# SCH_Flight-Computer-V3_2024-07-16.net
KiCad netlist of a schematic drawn in EasyEDA
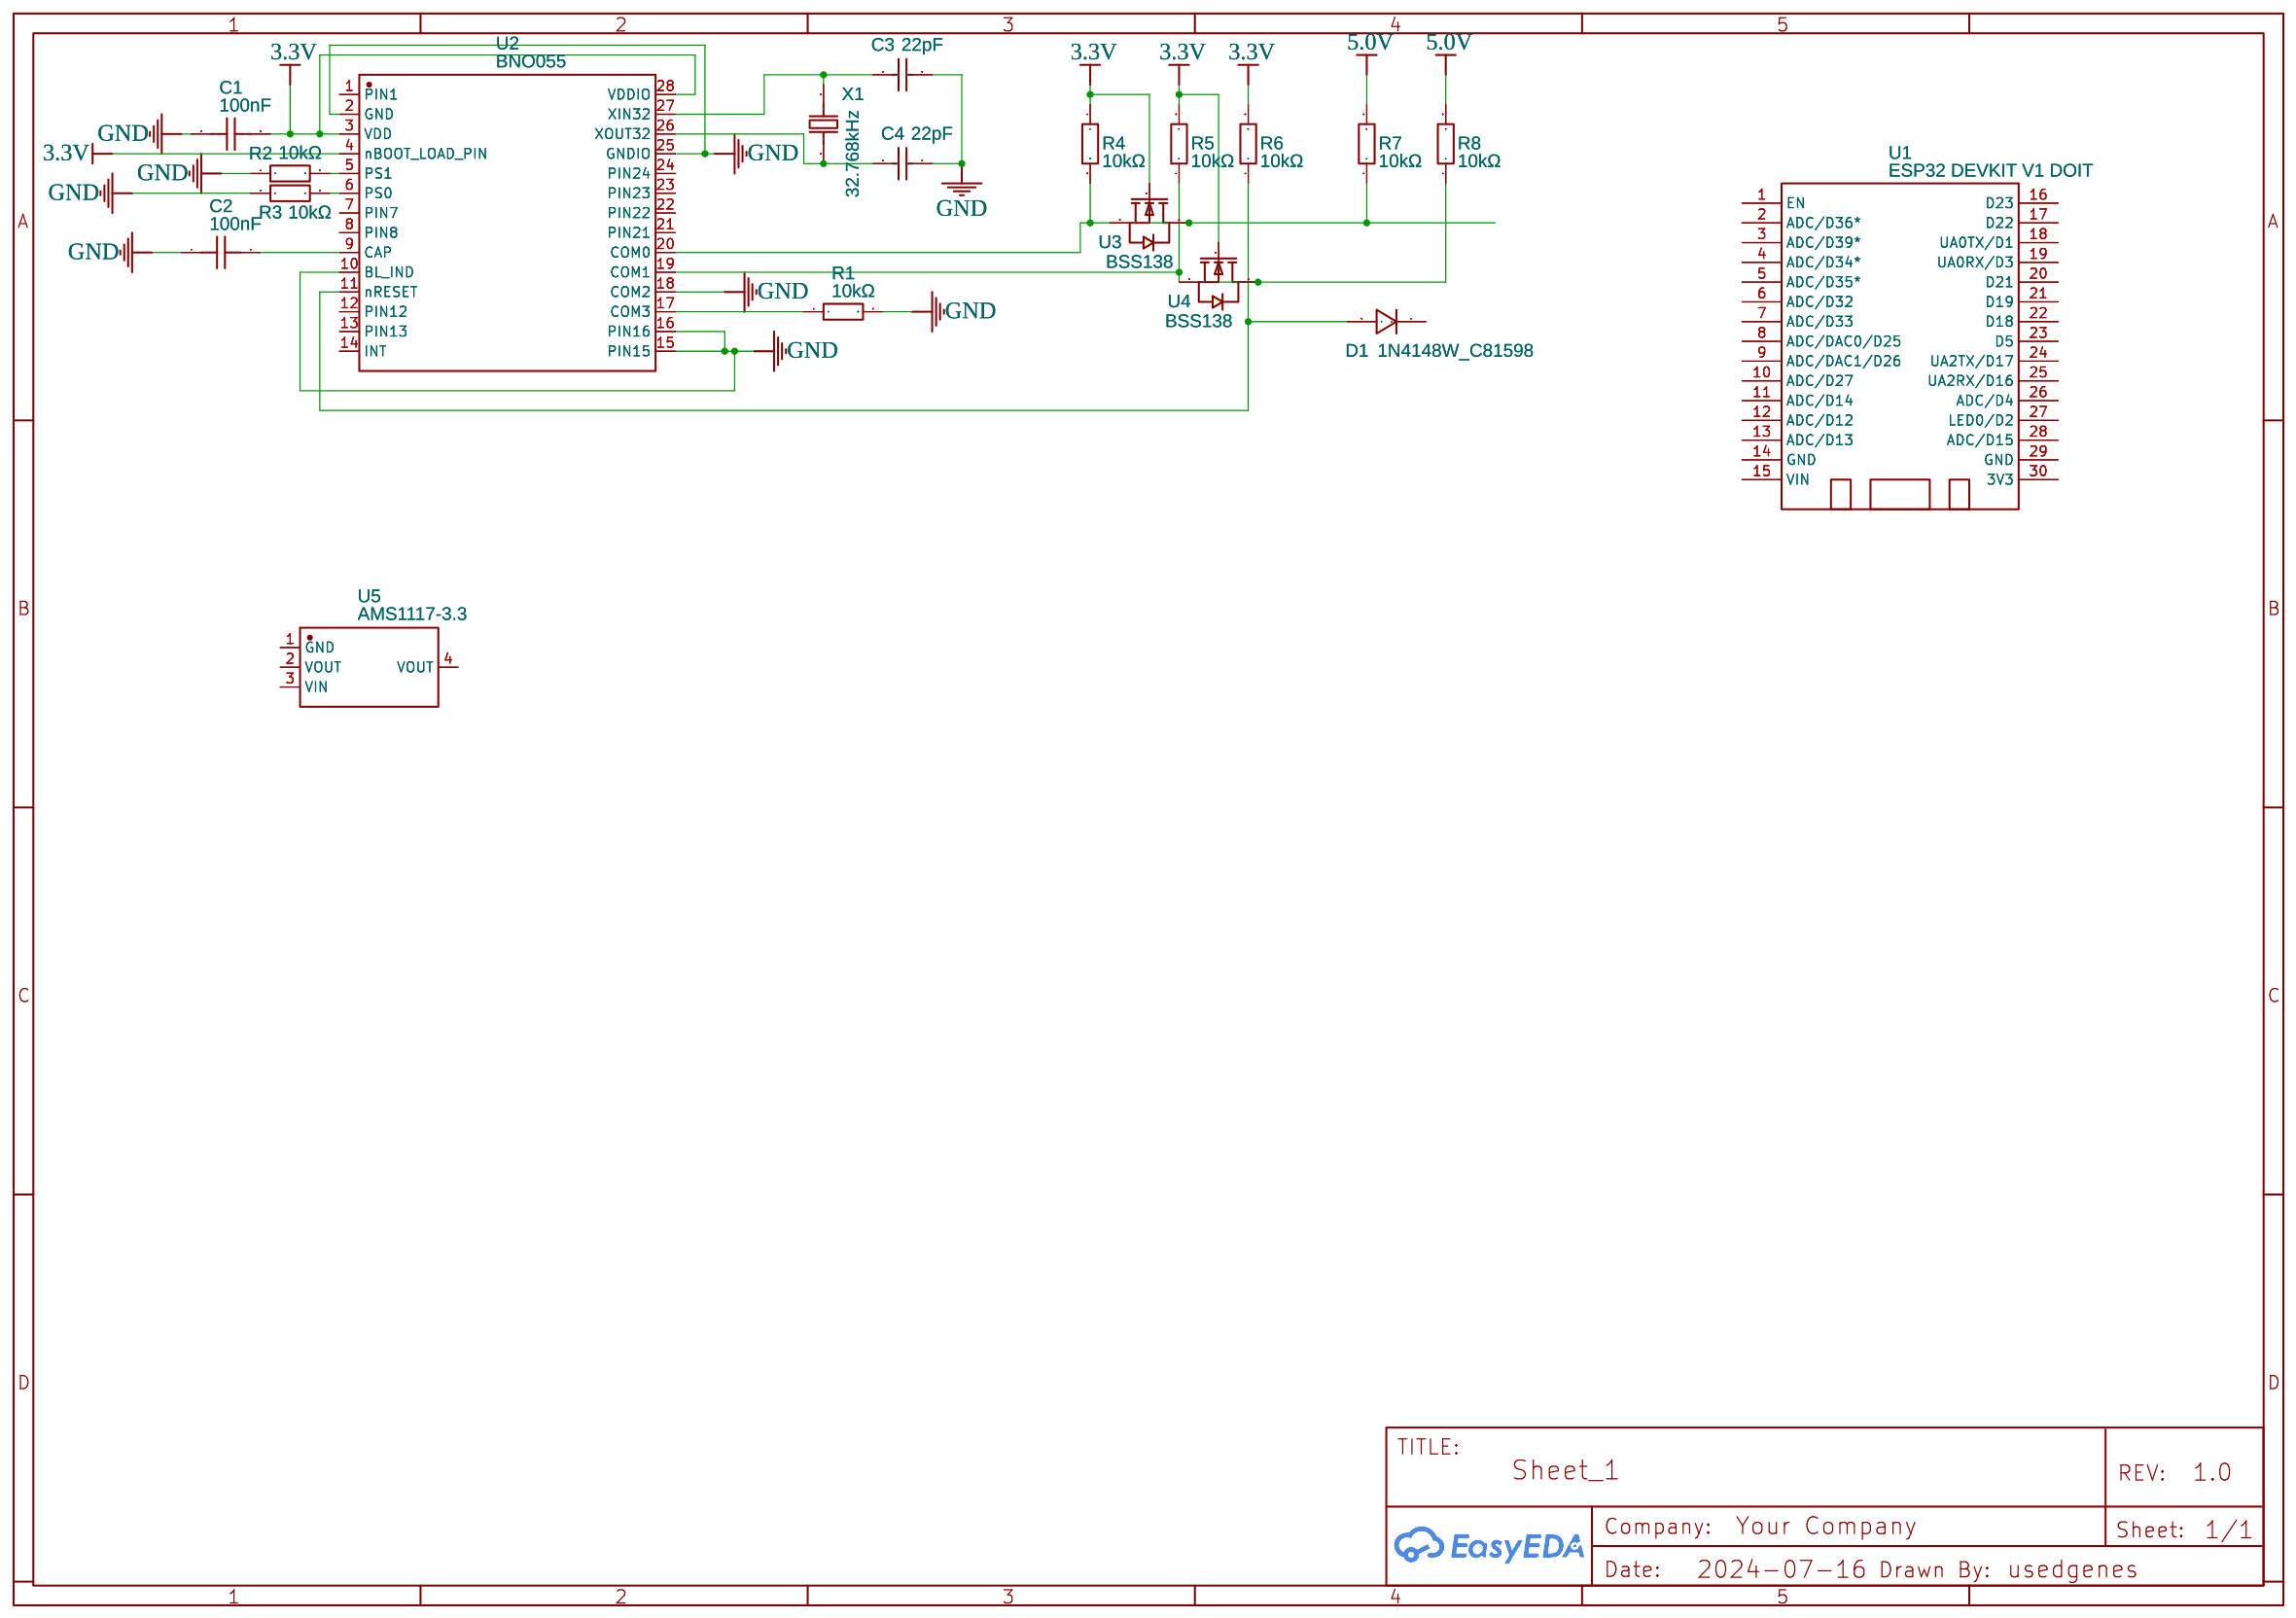
[diagram p0: schematic sheet]

(export (version "E")
  (design (tool "Eeschema 10.0.6"))
  (components
    (comp (ref "C1")
      (value "100nF")
      (fields
        (field (name "Manufacturer Part") "CC0603KRX7R9BB104")
        (field (name "Manufacturer") "YAGEO(国巨)")
      )
      (libsource (lib "") (part "CC0603KRX7R9BB104"))
    )
    (comp (ref "C2")
      (value "100nF")
      (fields
        (field (name "Manufacturer Part") "CC0603KRX7R9BB104")
        (field (name "Manufacturer") "YAGEO(国巨)")
      )
      (libsource (lib "") (part "CC0603KRX7R9BB104"))
    )
    (comp (ref "C3")
      (value "22pF")
      (fields (field (name "Manufacturer Part") "0402CG220J500NT") (field (name "Manufacturer") "FH(风华)"))
      (libsource (lib "") (part "0402CG220J500NT"))
    )
    (comp (ref "C4")
      (value "22pF")
      (fields (field (name "Manufacturer Part") "0402CG220J500NT") (field (name "Manufacturer") "FH(风华)"))
      (libsource (lib "") (part "0402CG220J500NT"))
    )
    (comp (ref "D1")
      (value "1N4148W_C81598")
      (fields (field (name "Manufacturer Part") "1N4148W") (field (name "Manufacturer") "ST(先科)"))
      (libsource (lib "") (part "1N4148W_C81598"))
    )
    (comp (ref "R1")
      (value "10kΩ")
      (fields
        (field (name "Manufacturer Part") "0402WGF1002TCE")
        (field (name "Manufacturer") "UNI-ROYAL(厚声)")
      )
      (libsource (lib "") (part "0402WGF1002TCE"))
    )
    (comp (ref "R2")
      (value "10kΩ")
      (fields
        (field (name "Manufacturer Part") "0402WGF1002TCE")
        (field (name "Manufacturer") "UNI-ROYAL(厚声)")
      )
      (libsource (lib "") (part "0402WGF1002TCE"))
    )
    (comp (ref "R3")
      (value "10kΩ")
      (fields
        (field (name "Manufacturer Part") "0402WGF1002TCE")
        (field (name "Manufacturer") "UNI-ROYAL(厚声)")
      )
      (libsource (lib "") (part "0402WGF1002TCE"))
    )
    (comp (ref "R4")
      (value "10kΩ")
      (fields
        (field (name "Manufacturer Part") "0402WGF1002TCE")
        (field (name "Manufacturer") "UNI-ROYAL(厚声)")
      )
      (libsource (lib "") (part "0402WGF1002TCE_2"))
    )
    (comp (ref "R5")
      (value "10kΩ")
      (fields
        (field (name "Manufacturer Part") "0402WGF1002TCE")
        (field (name "Manufacturer") "UNI-ROYAL(厚声)")
      )
      (libsource (lib "") (part "0402WGF1002TCE_1"))
    )
    (comp (ref "R6")
      (value "10kΩ")
      (fields
        (field (name "Manufacturer Part") "0402WGF1002TCE")
        (field (name "Manufacturer") "UNI-ROYAL(厚声)")
      )
      (libsource (lib "") (part "0402WGF1002TCE_1"))
    )
    (comp (ref "R7")
      (value "10kΩ")
      (fields
        (field (name "Manufacturer Part") "0402WGF1002TCE")
        (field (name "Manufacturer") "UNI-ROYAL(厚声)")
      )
      (libsource (lib "") (part "0402WGF1002TCE_1"))
    )
    (comp (ref "R8")
      (value "10kΩ")
      (fields
        (field (name "Manufacturer Part") "0402WGF1002TCE")
        (field (name "Manufacturer") "UNI-ROYAL(厚声)")
      )
      (libsource (lib "") (part "0402WGF1002TCE_1"))
    )
    (comp (ref "U1") (value "ESP32 DEVKIT V1 DOIT") (libsource (lib "") (part "ESP32 DEVKIT V1 DOIT")))
    (comp (ref "U2")
      (value "BNO055")
      (fields (field (name "Manufacturer") "Bosch(博世)"))
      (libsource (lib "") (part "BNO055"))
    )
    (comp (ref "U3")
      (value "BSS138")
      (fields (field (name "Manufacturer") "宏迦橙"))
      (libsource (lib "") (part "BSS138_C7420339"))
    )
    (comp (ref "U4")
      (value "BSS138")
      (fields (field (name "Manufacturer") "宏迦橙"))
      (libsource (lib "") (part "BSS138_C7420339"))
    )
    (comp (ref "U5")
      (value "AMS1117-3.3")
      (fields (field (name "Manufacturer") "AMS"))
      (libsource (lib "") (part "AMS1117-3.3"))
    )
    (comp (ref "X1")
      (value "32.768kHz")
      (fields
        (field (name "Manufacturer Part") "SC-32S32.768kHz20PPM12.5pF")
        (field (name "Manufacturer") "Seiko(精工)")
      )
      (libsource (lib "") (part "SC-32S32.768kHz20PPM12.5pF"))
    )
  )
  (nets
    (net (code "1") (name "3.3V") (class "Default")
      (node (ref "C1") (pin "2") (pinfunction "2_2") (pintype "unspecified"))
      (node (ref "R4") (pin "1") (pinfunction "1_1") (pintype "input"))
      (node (ref "R5") (pin "2") (pinfunction "2_2") (pintype "input"))
      (node (ref "R6") (pin "2") (pinfunction "2_2") (pintype "input"))
      (node (ref "U2") (pin "28") (pinfunction "VDDIO_28") (pintype "unspecified"))
      (node (ref "U2") (pin "3") (pinfunction "VDD_3") (pintype "unspecified"))
      (node (ref "U2") (pin "4") (pinfunction "nBOOT_LOAD_PIN_4") (pintype "unspecified"))
      (node (ref "U3") (pin "1") (pinfunction "G_1") (pintype "unspecified"))
      (node (ref "U4") (pin "1") (pinfunction "G_1") (pintype "unspecified"))
    )
    (net (code "2") (name "5.0V") (class "Default")
      (node (ref "R7") (pin "2") (pinfunction "2_2") (pintype "input"))
      (node (ref "R8") (pin "2") (pinfunction "2_2") (pintype "input"))
    )
    (net (code "3") (name "GND") (class "Default")
      (node (ref "C1") (pin "1") (pinfunction "1_1") (pintype "unspecified"))
      (node (ref "C2") (pin "1") (pinfunction "1_1") (pintype "unspecified"))
      (node (ref "C3") (pin "2") (pinfunction "2_2") (pintype "input"))
      (node (ref "C4") (pin "2") (pinfunction "2_2") (pintype "input"))
      (node (ref "R1") (pin "2") (pinfunction "2_2") (pintype "input"))
      (node (ref "R2") (pin "1") (pinfunction "1_1") (pintype "input"))
      (node (ref "R3") (pin "1") (pinfunction "1_1") (pintype "input"))
      (node (ref "U2") (pin "10") (pinfunction "BL_IND_10") (pintype "unspecified"))
      (node (ref "U2") (pin "15") (pinfunction "PIN15_15") (pintype "unspecified"))
      (node (ref "U2") (pin "16") (pinfunction "PIN16_16") (pintype "unspecified"))
      (node (ref "U2") (pin "18") (pinfunction "COM2_18") (pintype "unspecified"))
      (node (ref "U2") (pin "2") (pinfunction "GND_2") (pintype "unspecified"))
      (node (ref "U2") (pin "25") (pinfunction "GNDIO_25") (pintype "unspecified"))
    )
    (net (code "4") (name "Net-(D1-A)") (class "Default")
      (node (ref "D1") (pin "2") (pinfunction "A_2") (pintype "unspecified"))
      (node (ref "R6") (pin "1") (pinfunction "1_1") (pintype "input"))
      (node (ref "U2") (pin "11") (pinfunction "nRESET_11") (pintype "unspecified"))
    )
    (net (code "5") (name "Net-(U2-CAP)") (class "Default")
      (node (ref "C2") (pin "2") (pinfunction "2_2") (pintype "unspecified"))
      (node (ref "U2") (pin "9") (pinfunction "CAP_9") (pintype "unspecified"))
    )
    (net (code "6") (name "Net-(U2-COM0)") (class "Default")
      (node (ref "R4") (pin "2") (pinfunction "2_2") (pintype "input"))
      (node (ref "U2") (pin "20") (pinfunction "COM0_20") (pintype "unspecified"))
      (node (ref "U3") (pin "2") (pinfunction "S_2") (pintype "unspecified"))
    )
    (net (code "7") (name "Net-(U2-COM1)") (class "Default")
      (node (ref "R5") (pin "1") (pinfunction "1_1") (pintype "input"))
      (node (ref "U2") (pin "19") (pinfunction "COM1_19") (pintype "unspecified"))
      (node (ref "U4") (pin "2") (pinfunction "S_2") (pintype "unspecified"))
    )
    (net (code "8") (name "Net-(U2-COM3)") (class "Default")
      (node (ref "R1") (pin "1") (pinfunction "1_1") (pintype "input"))
      (node (ref "U2") (pin "17") (pinfunction "COM3_17") (pintype "unspecified"))
    )
    (net (code "9") (name "Net-(U2-PS0)") (class "Default")
      (node (ref "R3") (pin "2") (pinfunction "2_2") (pintype "input"))
      (node (ref "U2") (pin "6") (pinfunction "PS0_6") (pintype "unspecified"))
    )
    (net (code "10") (name "Net-(U2-PS1)") (class "Default")
      (node (ref "R2") (pin "2") (pinfunction "2_2") (pintype "input"))
      (node (ref "U2") (pin "5") (pinfunction "PS1_5") (pintype "unspecified"))
    )
    (net (code "11") (name "Net-(U2-XIN32)") (class "Default")
      (node (ref "C3") (pin "1") (pinfunction "1_1") (pintype "input"))
      (node (ref "U2") (pin "27") (pinfunction "XIN32_27") (pintype "unspecified"))
      (node (ref "X1") (pin "2") (pinfunction "2_2") (pintype "unspecified"))
    )
    (net (code "12") (name "Net-(U2-XOUT32)") (class "Default")
      (node (ref "C4") (pin "1") (pinfunction "1_1") (pintype "input"))
      (node (ref "U2") (pin "26") (pinfunction "XOUT32_26") (pintype "unspecified"))
      (node (ref "X1") (pin "1") (pinfunction "1_1") (pintype "unspecified"))
    )
    (net (code "13") (name "Net-(U3-D)") (class "Default")
      (node (ref "R7") (pin "1") (pinfunction "1_1") (pintype "input"))
      (node (ref "U3") (pin "3") (pinfunction "D_3") (pintype "unspecified"))
    )
    (net (code "14") (name "Net-(U4-D)") (class "Default")
      (node (ref "R8") (pin "1") (pinfunction "1_1") (pintype "input"))
      (node (ref "U4") (pin "3") (pinfunction "D_3") (pintype "unspecified"))
    )
    (net (code "15") (name "unconnected-(D1-K-Pad1)") (class "Default")
      (node (ref "D1") (pin "1") (pinfunction "K_1") (pintype "unspecified"))
    )
    (net (code "16") (name "unconnected-(U1-3V3-Pad30)") (class "Default")
      (node (ref "U1") (pin "30") (pinfunction "3V3_30") (pintype "bidirectional"))
    )
    (net (code "17") (name "unconnected-(U1-ADC{slash}D4-Pad26)") (class "Default")
      (node (ref "U1") (pin "26") (pinfunction "ADC/D4_26") (pintype "bidirectional"))
    )
    (net (code "18") (name "unconnected-(U1-ADC{slash}D12-Pad12)") (class "Default")
      (node (ref "U1") (pin "12") (pinfunction "ADC/D12_12") (pintype "bidirectional"))
    )
    (net (code "19") (name "unconnected-(U1-ADC{slash}D13-Pad13)") (class "Default")
      (node (ref "U1") (pin "13") (pinfunction "ADC/D13_13") (pintype "bidirectional"))
    )
    (net (code "20") (name "unconnected-(U1-ADC{slash}D14-Pad11)") (class "Default")
      (node (ref "U1") (pin "11") (pinfunction "ADC/D14_11") (pintype "bidirectional"))
    )
    (net (code "21") (name "unconnected-(U1-ADC{slash}D15-Pad28)") (class "Default")
      (node (ref "U1") (pin "28") (pinfunction "ADC/D15_28") (pintype "bidirectional"))
    )
    (net (code "22") (name "unconnected-(U1-ADC{slash}D27-Pad10)") (class "Default")
      (node (ref "U1") (pin "10") (pinfunction "ADC/D27_10") (pintype "bidirectional"))
    )
    (net (code "23") (name "unconnected-(U1-ADC{slash}D32-Pad6)") (class "Default")
      (node (ref "U1") (pin "6") (pinfunction "ADC/D32_6") (pintype "bidirectional"))
    )
    (net (code "24") (name "unconnected-(U1-ADC{slash}D33-Pad7)") (class "Default")
      (node (ref "U1") (pin "7") (pinfunction "ADC/D33_7") (pintype "bidirectional"))
    )
    (net (code "25") (name "unconnected-(U1-ADC{slash}D34*-Pad4)") (class "Default")
      (node (ref "U1") (pin "4") (pinfunction "ADC/D34*_4") (pintype "input"))
    )
    (net (code "26") (name "unconnected-(U1-ADC{slash}D35*-Pad5)") (class "Default")
      (node (ref "U1") (pin "5") (pinfunction "ADC/D35*_5") (pintype "input"))
    )
    (net (code "27") (name "unconnected-(U1-ADC{slash}D36*-Pad2)") (class "Default")
      (node (ref "U1") (pin "2") (pinfunction "ADC/D36*_2") (pintype "input"))
    )
    (net (code "28") (name "unconnected-(U1-ADC{slash}D39*-Pad3)") (class "Default")
      (node (ref "U1") (pin "3") (pinfunction "ADC/D39*_3") (pintype "input"))
    )
    (net (code "29") (name "unconnected-(U1-ADC{slash}DAC0{slash}D25-Pad8)") (class "Default")
      (node (ref "U1") (pin "8") (pinfunction "ADC/DAC0/D25_8") (pintype "bidirectional"))
    )
    (net (code "30") (name "unconnected-(U1-ADC{slash}DAC1{slash}D26-Pad9)") (class "Default")
      (node (ref "U1") (pin "9") (pinfunction "ADC/DAC1/D26_9") (pintype "bidirectional"))
    )
    (net (code "31") (name "unconnected-(U1-D5-Pad23)") (class "Default")
      (node (ref "U1") (pin "23") (pinfunction "D5_23") (pintype "bidirectional"))
    )
    (net (code "32") (name "unconnected-(U1-D18-Pad22)") (class "Default")
      (node (ref "U1") (pin "22") (pinfunction "D18_22") (pintype "bidirectional"))
    )
    (net (code "33") (name "unconnected-(U1-D19-Pad21)") (class "Default")
      (node (ref "U1") (pin "21") (pinfunction "D19_21") (pintype "bidirectional"))
    )
    (net (code "34") (name "unconnected-(U1-D21-Pad20)") (class "Default")
      (node (ref "U1") (pin "20") (pinfunction "D21_20") (pintype "bidirectional"))
    )
    (net (code "35") (name "unconnected-(U1-D22-Pad17)") (class "Default")
      (node (ref "U1") (pin "17") (pinfunction "D22_17") (pintype "bidirectional"))
    )
    (net (code "36") (name "unconnected-(U1-D23-Pad16)") (class "Default")
      (node (ref "U1") (pin "16") (pinfunction "D23_16") (pintype "bidirectional"))
    )
    (net (code "37") (name "unconnected-(U1-EN-Pad1)") (class "Default")
      (node (ref "U1") (pin "1") (pinfunction "EN_1") (pintype "bidirectional"))
    )
    (net (code "38") (name "unconnected-(U1-GND-Pad14)") (class "Default")
      (node (ref "U1") (pin "14") (pinfunction "GND_14") (pintype "bidirectional"))
    )
    (net (code "39") (name "unconnected-(U1-GND-Pad29)") (class "Default")
      (node (ref "U1") (pin "29") (pinfunction "GND_29") (pintype "bidirectional"))
    )
    (net (code "40") (name "unconnected-(U1-LED0{slash}D2-Pad27)") (class "Default")
      (node (ref "U1") (pin "27") (pinfunction "LED0/D2_27") (pintype "bidirectional"))
    )
    (net (code "41") (name "unconnected-(U1-UA0RX{slash}D3-Pad19)") (class "Default")
      (node (ref "U1") (pin "19") (pinfunction "UA0RX/D3_19") (pintype "bidirectional"))
    )
    (net (code "42") (name "unconnected-(U1-UA0TX{slash}D1-Pad18)") (class "Default")
      (node (ref "U1") (pin "18") (pinfunction "UA0TX/D1_18") (pintype "bidirectional"))
    )
    (net (code "43") (name "unconnected-(U1-UA2RX{slash}D16-Pad25)") (class "Default")
      (node (ref "U1") (pin "25") (pinfunction "UA2RX/D16_25") (pintype "bidirectional"))
    )
    (net (code "44") (name "unconnected-(U1-UA2TX{slash}D17-Pad24)") (class "Default")
      (node (ref "U1") (pin "24") (pinfunction "UA2TX/D17_24") (pintype "bidirectional"))
    )
    (net (code "45") (name "unconnected-(U1-VIN-Pad15)") (class "Default")
      (node (ref "U1") (pin "15") (pinfunction "VIN_15") (pintype "input"))
    )
    (net (code "46") (name "unconnected-(U2-INT-Pad14)") (class "Default")
      (node (ref "U2") (pin "14") (pinfunction "INT_14") (pintype "unspecified"))
    )
    (net (code "47") (name "unconnected-(U2-PIN1-Pad1)") (class "Default")
      (node (ref "U2") (pin "1") (pinfunction "PIN1_1") (pintype "unspecified"))
    )
    (net (code "48") (name "unconnected-(U2-PIN7-Pad7)") (class "Default")
      (node (ref "U2") (pin "7") (pinfunction "PIN7_7") (pintype "unspecified"))
    )
    (net (code "49") (name "unconnected-(U2-PIN8-Pad8)") (class "Default")
      (node (ref "U2") (pin "8") (pinfunction "PIN8_8") (pintype "unspecified"))
    )
    (net (code "50") (name "unconnected-(U2-PIN12-Pad12)") (class "Default")
      (node (ref "U2") (pin "12") (pinfunction "PIN12_12") (pintype "unspecified"))
    )
    (net (code "51") (name "unconnected-(U2-PIN13-Pad13)") (class "Default")
      (node (ref "U2") (pin "13") (pinfunction "PIN13_13") (pintype "unspecified"))
    )
    (net (code "52") (name "unconnected-(U2-PIN21-Pad21)") (class "Default")
      (node (ref "U2") (pin "21") (pinfunction "PIN21_21") (pintype "unspecified"))
    )
    (net (code "53") (name "unconnected-(U2-PIN22-Pad22)") (class "Default")
      (node (ref "U2") (pin "22") (pinfunction "PIN22_22") (pintype "unspecified"))
    )
    (net (code "54") (name "unconnected-(U2-PIN23-Pad23)") (class "Default")
      (node (ref "U2") (pin "23") (pinfunction "PIN23_23") (pintype "unspecified"))
    )
    (net (code "55") (name "unconnected-(U2-PIN24-Pad24)") (class "Default")
      (node (ref "U2") (pin "24") (pinfunction "PIN24_24") (pintype "unspecified"))
    )
    (net (code "56") (name "unconnected-(U5-GND-Pad1)") (class "Default")
      (node (ref "U5") (pin "1") (pinfunction "GND_1") (pintype "unspecified"))
    )
    (net (code "57") (name "unconnected-(U5-VIN-Pad3)") (class "Default")
      (node (ref "U5") (pin "3") (pinfunction "VIN_3") (pintype "unspecified"))
    )
    (net (code "58") (name "unconnected-(U5-VOUT-Pad2)") (class "Default")
      (node (ref "U5") (pin "2") (pinfunction "VOUT_2") (pintype "unspecified"))
    )
    (net (code "59") (name "unconnected-(U5-VOUT-Pad4)") (class "Default")
      (node (ref "U5") (pin "4") (pinfunction "VOUT_4") (pintype "unspecified"))
    )
  )
)
